# bitbox_rev2_06_sym.net
KiCad netlist of a schematic drawn in EAGLE
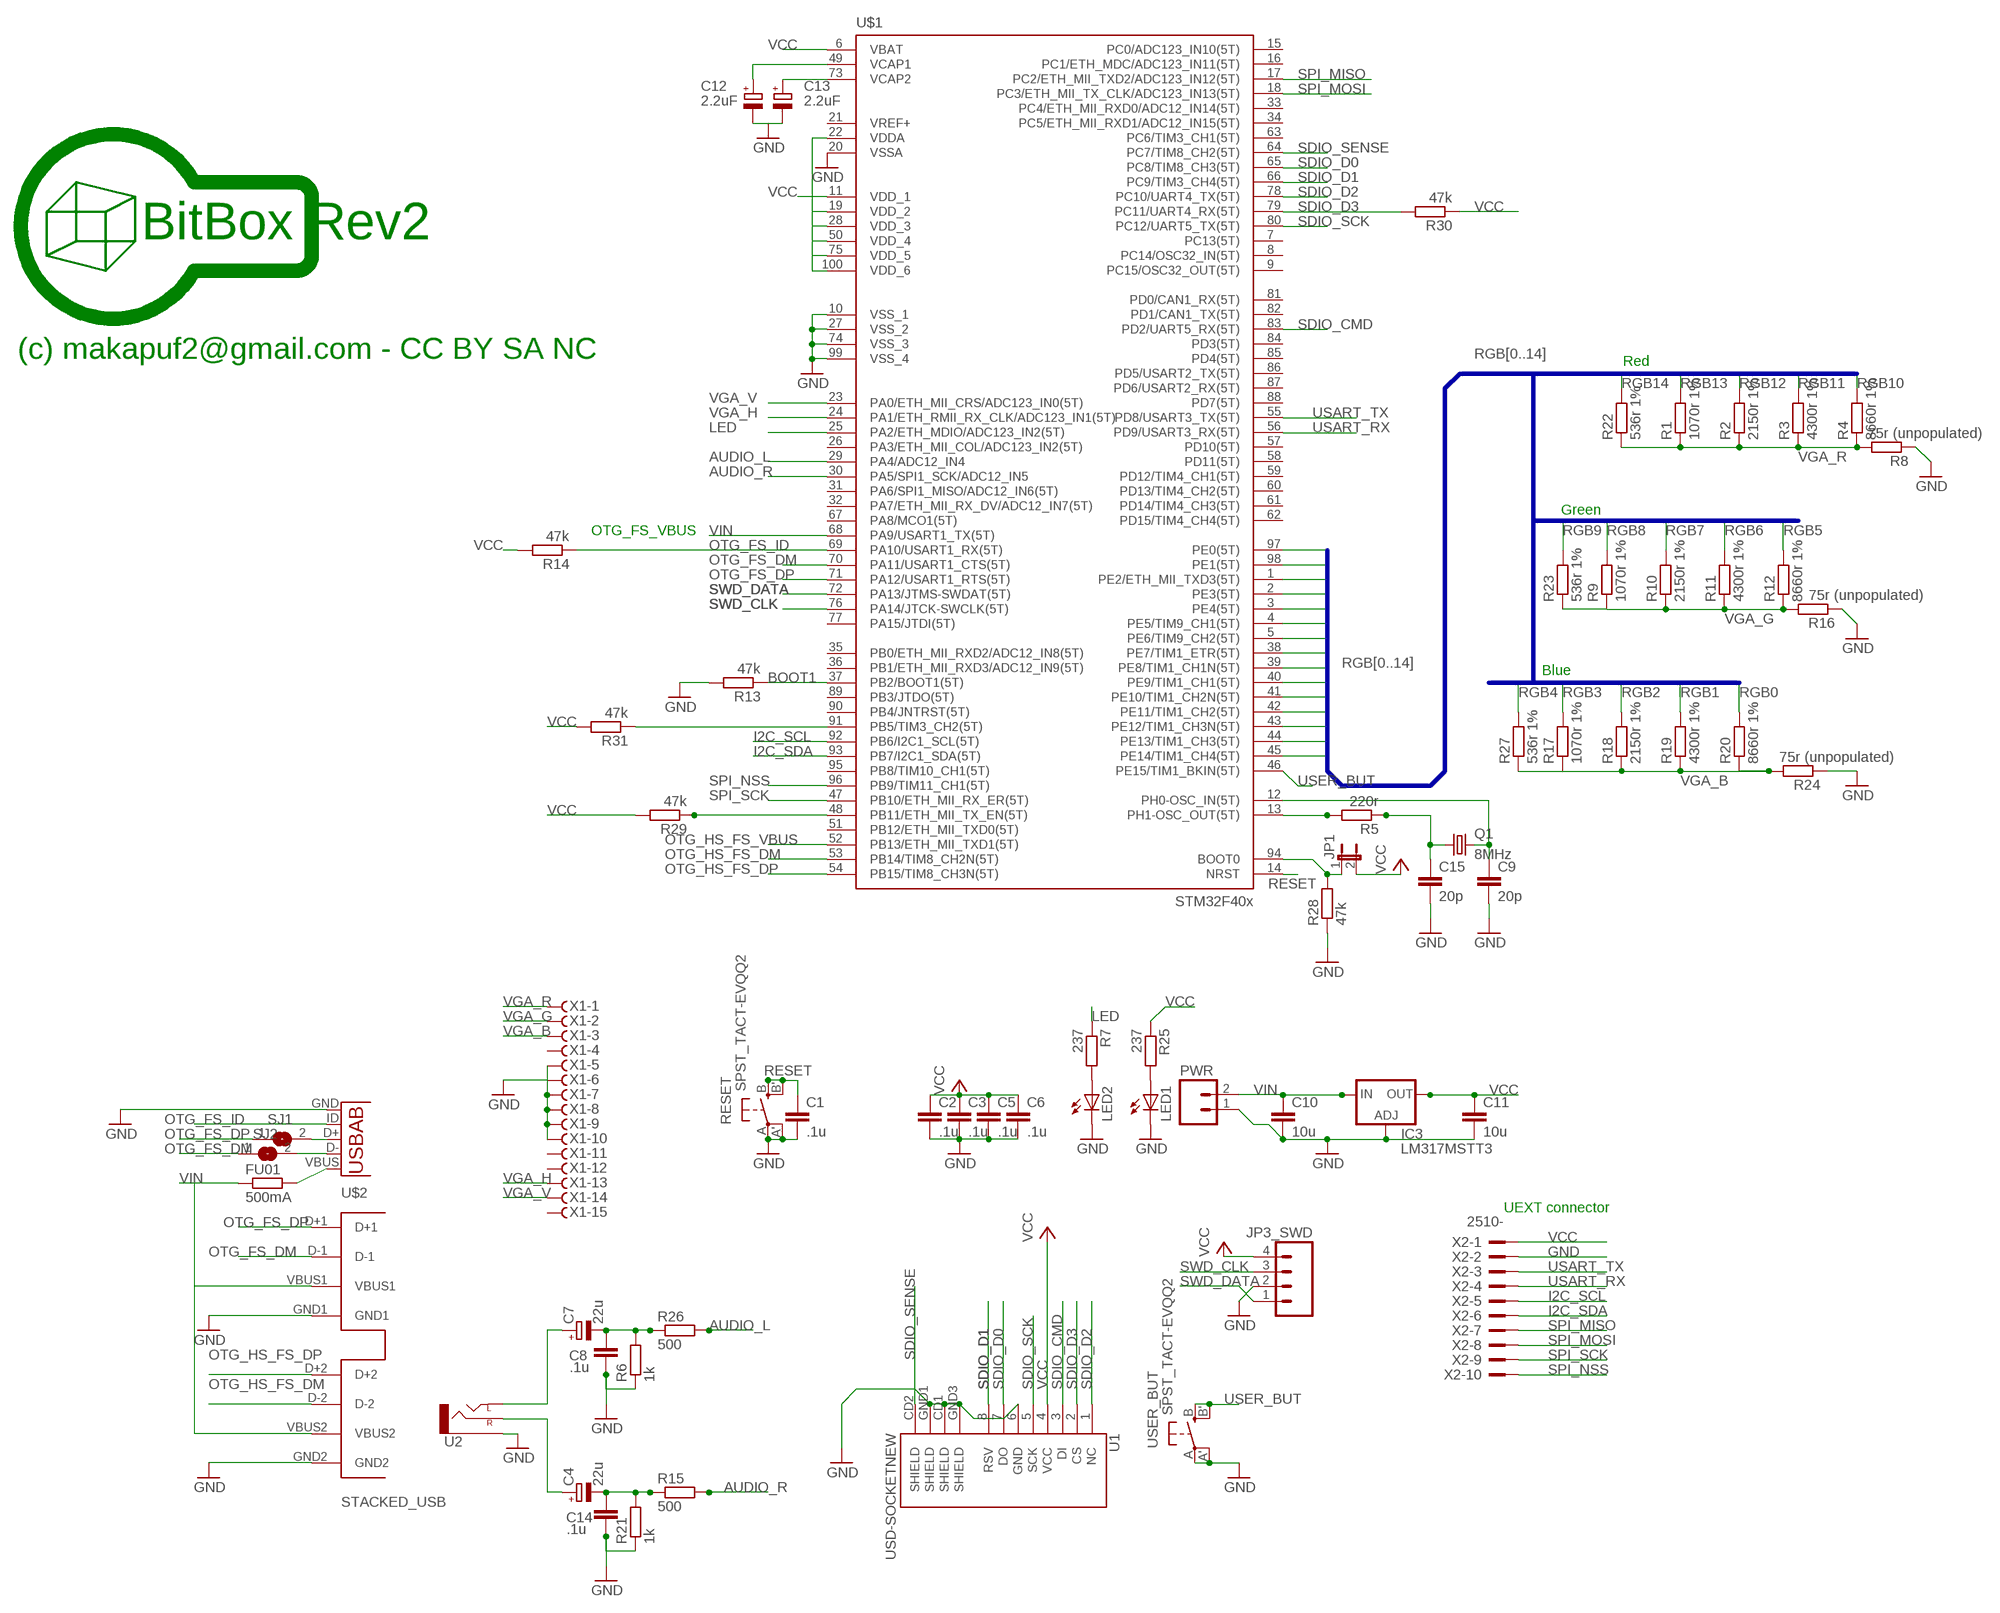
[diagram p0: schematic, sheet 1]

(export (version "E")
  (design (tool "Eeschema 10.0.6"))
  (components
    (comp (ref "C1")
      (value ".1u")
      (footprint "eagle-import:C0603")
      (libsource (lib "eagle-import") (part "C-EUC0603"))
    )
    (comp (ref "C2")
      (value ".1u")
      (footprint "eagle-import:C0603")
      (libsource (lib "eagle-import") (part "C-EUC0603"))
    )
    (comp (ref "C3")
      (value ".1u")
      (footprint "eagle-import:C0603")
      (libsource (lib "eagle-import") (part "C-EUC0603"))
    )
    (comp (ref "C4")
      (value "22u")
      (footprint "eagle-import:153CLV-0505")
      (libsource (lib "eagle-import") (part "CPOL-EU153CLV-0505"))
    )
    (comp (ref "C5")
      (value ".1u")
      (footprint "eagle-import:C0603")
      (libsource (lib "eagle-import") (part "C-EUC0603"))
    )
    (comp (ref "C6")
      (value ".1u")
      (footprint "eagle-import:C0603")
      (libsource (lib "eagle-import") (part "C-EUC0603"))
    )
    (comp (ref "C7")
      (value "22u")
      (footprint "eagle-import:153CLV-0505")
      (libsource (lib "eagle-import") (part "CPOL-EU153CLV-0505"))
    )
    (comp (ref "C8")
      (value ".1u")
      (footprint "eagle-import:C0603")
      (libsource (lib "eagle-import") (part "C-EUC0603"))
    )
    (comp (ref "C9")
      (value "20p")
      (footprint "eagle-import:C0603")
      (libsource (lib "eagle-import") (part "C-EUC0603"))
    )
    (comp (ref "C10")
      (value "10u")
      (footprint "eagle-import:C1206")
      (libsource (lib "eagle-import") (part "C-EUC1206"))
    )
    (comp (ref "C11")
      (value "10u")
      (footprint "eagle-import:C1206")
      (libsource (lib "eagle-import") (part "C-EUC1206"))
    )
    (comp (ref "C12")
      (value "2.2uF")
      (footprint "eagle-import:SMC_B")
      (libsource (lib "eagle-import") (part "CPOL-EUSMCB"))
    )
    (comp (ref "C13")
      (value "2.2uF")
      (footprint "eagle-import:SMC_B")
      (libsource (lib "eagle-import") (part "CPOL-EUSMCB"))
    )
    (comp (ref "C14")
      (value ".1u")
      (footprint "eagle-import:C0603")
      (libsource (lib "eagle-import") (part "C-EUC0603"))
    )
    (comp (ref "C15")
      (value "20p")
      (footprint "eagle-import:C0603")
      (libsource (lib "eagle-import") (part "C-EUC0603"))
    )
    (comp (ref "FU01")
      (value "500mA")
      (footprint "eagle-import:R1206")
      (libsource (lib "eagle-import") (part "R-EU_R1206"))
    )
    (comp (ref "IC3")
      (value "LM317MSTT3")
      (footprint "eagle-import:SOT223")
      (libsource (lib "eagle-import") (part "LM317?MSTT3"))
    )
    (comp (ref "JP1")
      (value "JP1E")
      (footprint "eagle-import:JP1")
      (libsource (lib "eagle-import") (part "JP1E"))
    )
    (comp (ref "JP3_SWD")
      (value "M04PTH")
      (footprint "eagle-import:1X04")
      (libsource (lib "eagle-import") (part "M04PTH"))
    )
    (comp (ref "LED1")
      (value "LEDCHIPLED_0805")
      (footprint "eagle-import:CHIPLED_0805")
      (libsource (lib "eagle-import") (part "LEDCHIPLED_0805"))
    )
    (comp (ref "LED2")
      (value "LEDCHIPLED_0805")
      (footprint "eagle-import:CHIPLED_0805")
      (libsource (lib "eagle-import") (part "LEDCHIPLED_0805"))
    )
    (comp (ref "PWR")
      (value "M02PTH")
      (footprint "eagle-import:1X02")
      (libsource (lib "eagle-import") (part "M02PTH"))
    )
    (comp (ref "Q1")
      (value "8MHz")
      (footprint "eagle-import:SM49")
      (fields (field (name "OC_FARNELL") "unknown"))
      (libsource (lib "eagle-import") (part "CRYSTALSM49"))
    )
    (comp (ref "R1")
      (value "1070r 1%")
      (footprint "eagle-import:R0603")
      (libsource (lib "eagle-import") (part "R-EU_R0603"))
    )
    (comp (ref "R2")
      (value "2150r 1%")
      (footprint "eagle-import:R0603")
      (libsource (lib "eagle-import") (part "R-EU_R0603"))
    )
    (comp (ref "R3")
      (value "4300r 1%")
      (footprint "eagle-import:R0603")
      (libsource (lib "eagle-import") (part "R-EU_R0603"))
    )
    (comp (ref "R4")
      (value "8660r 1%")
      (footprint "eagle-import:R0603")
      (libsource (lib "eagle-import") (part "R-EU_R0603"))
    )
    (comp (ref "R5")
      (value "220r")
      (footprint "eagle-import:R0603")
      (libsource (lib "eagle-import") (part "R-EU_R0603"))
    )
    (comp (ref "R6")
      (value "1k")
      (footprint "eagle-import:R0603")
      (libsource (lib "eagle-import") (part "R-EU_R0603"))
    )
    (comp (ref "R7")
      (value "237")
      (footprint "eagle-import:R0603")
      (libsource (lib "eagle-import") (part "R-EU_R0603"))
    )
    (comp (ref "R8")
      (value "75r (unpopulated)")
      (footprint "eagle-import:R0603")
      (libsource (lib "eagle-import") (part "R-EU_R0603"))
    )
    (comp (ref "R9")
      (value "1070r 1%")
      (footprint "eagle-import:R0603")
      (libsource (lib "eagle-import") (part "R-EU_R0603"))
    )
    (comp (ref "R10")
      (value "2150r 1%")
      (footprint "eagle-import:R0603")
      (libsource (lib "eagle-import") (part "R-EU_R0603"))
    )
    (comp (ref "R11")
      (value "4300r 1%")
      (footprint "eagle-import:R0603")
      (libsource (lib "eagle-import") (part "R-EU_R0603"))
    )
    (comp (ref "R12")
      (value "8660r 1%")
      (footprint "eagle-import:R0603")
      (libsource (lib "eagle-import") (part "R-EU_R0603"))
    )
    (comp (ref "R13")
      (value "47k")
      (footprint "eagle-import:R0603")
      (libsource (lib "eagle-import") (part "R-EU_R0603"))
    )
    (comp (ref "R14")
      (value "47k")
      (footprint "eagle-import:R0603")
      (libsource (lib "eagle-import") (part "R-EU_R0603"))
    )
    (comp (ref "R15")
      (value "500")
      (footprint "eagle-import:R0603")
      (libsource (lib "eagle-import") (part "R-EU_R0603"))
    )
    (comp (ref "R16")
      (value "75r (unpopulated)")
      (footprint "eagle-import:R0603")
      (libsource (lib "eagle-import") (part "R-EU_R0603"))
    )
    (comp (ref "R17")
      (value "1070r 1%")
      (footprint "eagle-import:R0603")
      (libsource (lib "eagle-import") (part "R-EU_R0603"))
    )
    (comp (ref "R18")
      (value "2150r 1%")
      (footprint "eagle-import:R0603")
      (libsource (lib "eagle-import") (part "R-EU_R0603"))
    )
    (comp (ref "R19")
      (value "4300r 1%")
      (footprint "eagle-import:R0603")
      (libsource (lib "eagle-import") (part "R-EU_R0603"))
    )
    (comp (ref "R20")
      (value "8660r 1%")
      (footprint "eagle-import:R0603")
      (libsource (lib "eagle-import") (part "R-EU_R0603"))
    )
    (comp (ref "R21")
      (value "1k")
      (footprint "eagle-import:R0603")
      (libsource (lib "eagle-import") (part "R-EU_R0603"))
    )
    (comp (ref "R22")
      (value "536r 1%")
      (footprint "eagle-import:R0603")
      (libsource (lib "eagle-import") (part "R-EU_R0603"))
    )
    (comp (ref "R23")
      (value "536r 1%")
      (footprint "eagle-import:R0603")
      (libsource (lib "eagle-import") (part "R-EU_R0603"))
    )
    (comp (ref "R24")
      (value "75r (unpopulated)")
      (footprint "eagle-import:R0603")
      (libsource (lib "eagle-import") (part "R-EU_R0603"))
    )
    (comp (ref "R25")
      (value "237")
      (footprint "eagle-import:R0603")
      (libsource (lib "eagle-import") (part "R-EU_R0603"))
    )
    (comp (ref "R26")
      (value "500")
      (footprint "eagle-import:R0603")
      (libsource (lib "eagle-import") (part "R-EU_R0603"))
    )
    (comp (ref "R27")
      (value "536r 1%")
      (footprint "eagle-import:R0603")
      (libsource (lib "eagle-import") (part "R-EU_R0603"))
    )
    (comp (ref "R28")
      (value "47k")
      (footprint "eagle-import:R0603")
      (libsource (lib "eagle-import") (part "R-EU_R0603"))
    )
    (comp (ref "R29")
      (value "47k")
      (footprint "eagle-import:R0603")
      (libsource (lib "eagle-import") (part "R-EU_R0603"))
    )
    (comp (ref "R30")
      (value "47k")
      (footprint "eagle-import:R0603")
      (libsource (lib "eagle-import") (part "R-EU_R0603"))
    )
    (comp (ref "R31")
      (value "47k")
      (footprint "eagle-import:R0603")
      (libsource (lib "eagle-import") (part "R-EU_R0603"))
    )
    (comp (ref "RESET")
      (value "SPST_TACT-EVQQ2")
      (footprint "eagle-import:EVQ-Q2")
      (libsource (lib "eagle-import") (part "SPST_TACT-EVQQ2"))
    )
    (comp (ref "SJ1") (value "SJ") (footprint "eagle-import:SJ") (libsource (lib "eagle-import") (part "SJ")))
    (comp (ref "SJ2") (value "SJ") (footprint "eagle-import:SJ") (libsource (lib "eagle-import") (part "SJ")))
    (comp (ref "U$1")
      (value "STM32F407V")
      (footprint "eagle-import:TQFP100")
      (libsource (lib "eagle-import") (part "STM32F407V"))
    )
    (comp (ref "U$2")
      (value "STACKED_USB")
      (footprint "eagle-import:2STACKED")
      (libsource (lib "eagle-import") (part "STACKED_USB"))
    )
    (comp (ref "U1")
      (value "USD-SOCKETNEW")
      (footprint "eagle-import:MICRO-SD-SOCKET-PP")
      (libsource (lib "eagle-import") (part "USD-SOCKETNEW"))
    )
    (comp (ref "U2")
      (value "AUDIO-JACKPTH")
      (footprint "eagle-import:AUDIO-JACK")
      (libsource (lib "eagle-import") (part "AUDIO-JACKPTH"))
    )
    (comp (ref "U3")
      (value "USB-AB")
      (footprint "eagle-import:USB-AB-MICRO-SMD")
      (libsource (lib "eagle-import") (part "USB-AB"))
    )
    (comp (ref "USER_BUT")
      (value "SPST_TACT-EVQQ2")
      (footprint "eagle-import:EVQ-Q2")
      (libsource (lib "eagle-import") (part "SPST_TACT-EVQQ2"))
    )
    (comp (ref "X1")
      (value "HF15HS")
      (footprint "eagle-import:HDF15H")
      (libsource (lib "eagle-import") (part "HF15?SH"))
    )
    (comp (ref "X2")
      (value "2510-")
      (footprint "eagle-import:PAK100_2500-10")
      (fields (field (name "MF") "3M") (field (name "MPN") "2510-6002UB"))
      (libsource (lib "eagle-import") (part "2510-"))
    )
  )
  (nets
    (net (code "1") (name "/AUDIO_L") (class "Default")
      (node (ref "R26") (pin "2") (pinfunction "2_2") (pintype "passive"))
      (node (ref "U$1") (pin "29") (pinfunction "PA4/ADC12_IN4_29") (pintype "bidirectional"))
    )
    (net (code "2") (name "/AUDIO_R") (class "Default")
      (node (ref "R15") (pin "2") (pinfunction "2_2") (pintype "passive"))
      (node (ref "U$1") (pin "30") (pinfunction "PA5/SPI1_SCK/ADC12_IN5_30") (pintype "bidirectional"))
    )
    (net (code "3") (name "/BOOT1") (class "Default")
      (node (ref "R13") (pin "1") (pinfunction "1_1") (pintype "passive"))
      (node (ref "U$1") (pin "37") (pinfunction "PB2/BOOT1(5T)_37") (pintype "bidirectional"))
    )
    (net (code "4") (name "/I2C_SCL") (class "Default")
      (node (ref "U$1") (pin "92") (pinfunction "PB6/I2C1_SCL(5T)_92") (pintype "bidirectional"))
      (node (ref "X2") (pin "5") (pinfunction "KL_5") (pintype "passive"))
    )
    (net (code "5") (name "/I2C_SDA") (class "Default")
      (node (ref "U$1") (pin "93") (pinfunction "PB7/I2C1_SDA(5T)_93") (pintype "bidirectional"))
      (node (ref "X2") (pin "6") (pinfunction "KL_6") (pintype "passive"))
    )
    (net (code "6") (name "/LED") (class "Default")
      (node (ref "R7") (pin "1") (pinfunction "1_1") (pintype "passive"))
      (node (ref "U$1") (pin "25") (pinfunction "PA2/ETH_MDIO/ADC123_IN2(5T)_25") (pintype "bidirectional"))
    )
    (net (code "7") (name "/OTG_FS_DM") (class "Default")
      (node (ref "SJ2") (pin "1") (pinfunction "1_1") (pintype "passive"))
      (node (ref "U$1") (pin "70") (pinfunction "PA11/USART1_CTS(5T)_70") (pintype "bidirectional"))
      (node (ref "U$2") (pin "D-1") (pinfunction "D-1_D-1") (pintype "bidirectional"))
    )
    (net (code "8") (name "/OTG_FS_DP") (class "Default")
      (node (ref "SJ1") (pin "1") (pinfunction "1_1") (pintype "passive"))
      (node (ref "U$1") (pin "71") (pinfunction "PA12/USART1_RTS(5T)_71") (pintype "bidirectional"))
      (node (ref "U$2") (pin "D+1") (pinfunction "D+1_D+1") (pintype "bidirectional"))
    )
    (net (code "9") (name "/OTG_FS_ID") (class "Default")
      (node (ref "R14") (pin "1") (pinfunction "1_1") (pintype "passive"))
      (node (ref "U$1") (pin "69") (pinfunction "PA10/USART1_RX(5T)_69") (pintype "bidirectional"))
      (node (ref "U3") (pin "ID") (pinfunction "USBID_ID") (pintype "bidirectional"))
    )
    (net (code "10") (name "/OTG_HS_FS_DM") (class "Default")
      (node (ref "U$1") (pin "53") (pinfunction "PB14/TIM8_CH2N(5T)_53") (pintype "bidirectional"))
      (node (ref "U$2") (pin "D-2") (pinfunction "D-2_D-2") (pintype "bidirectional"))
    )
    (net (code "11") (name "/OTG_HS_FS_DP") (class "Default")
      (node (ref "U$1") (pin "54") (pinfunction "PB15/TIM8_CH3N(5T)_54") (pintype "bidirectional"))
      (node (ref "U$2") (pin "D+2") (pinfunction "D+2_D+2") (pintype "bidirectional"))
    )
    (net (code "12") (name "/OTG_HS_FS_VBUS") (class "Default")
      (node (ref "U$1") (pin "52") (pinfunction "PB13/ETH_MII_TXD1(5T)_52") (pintype "bidirectional"))
    )
    (net (code "13") (name "/RESET") (class "Default")
      (node (ref "C1") (pin "1") (pinfunction "1_1") (pintype "passive"))
      (node (ref "RESET") (pin "B") (pinfunction "S_B") (pintype "passive"))
      (node (ref "RESET") (pin "B'") (pinfunction "S1_B'") (pintype "passive"))
      (node (ref "U$1") (pin "14") (pinfunction "NRST_14") (pintype "bidirectional"))
    )
    (net (code "14") (name "/RGB0") (class "Default")
      (node (ref "R20") (pin "2") (pinfunction "2_2") (pintype "passive"))
      (node (ref "U$1") (pin "97") (pinfunction "PE0(5T)_97") (pintype "bidirectional"))
    )
    (net (code "15") (name "/RGB1") (class "Default")
      (node (ref "R19") (pin "2") (pinfunction "2_2") (pintype "passive"))
      (node (ref "U$1") (pin "98") (pinfunction "PE1(5T)_98") (pintype "bidirectional"))
    )
    (net (code "16") (name "/RGB2") (class "Default")
      (node (ref "R18") (pin "2") (pinfunction "2_2") (pintype "passive"))
      (node (ref "U$1") (pin "1") (pinfunction "PE2/ETH_MII_TXD3(5T)_1") (pintype "bidirectional"))
    )
    (net (code "17") (name "/RGB3") (class "Default")
      (node (ref "R17") (pin "2") (pinfunction "2_2") (pintype "passive"))
      (node (ref "U$1") (pin "2") (pinfunction "PE3(5T)_2") (pintype "bidirectional"))
    )
    (net (code "18") (name "/RGB4") (class "Default")
      (node (ref "R27") (pin "2") (pinfunction "2_2") (pintype "passive"))
      (node (ref "U$1") (pin "3") (pinfunction "PE4(5T)_3") (pintype "bidirectional"))
    )
    (net (code "19") (name "/RGB5") (class "Default")
      (node (ref "R12") (pin "2") (pinfunction "2_2") (pintype "passive"))
      (node (ref "U$1") (pin "4") (pinfunction "PE5/TIM9_CH1(5T)_4") (pintype "bidirectional"))
    )
    (net (code "20") (name "/RGB6") (class "Default")
      (node (ref "R11") (pin "2") (pinfunction "2_2") (pintype "passive"))
      (node (ref "U$1") (pin "5") (pinfunction "PE6/TIM9_CH2(5T)_5") (pintype "bidirectional"))
    )
    (net (code "21") (name "/RGB7") (class "Default")
      (node (ref "R10") (pin "2") (pinfunction "2_2") (pintype "passive"))
      (node (ref "U$1") (pin "38") (pinfunction "PE7/TIM1_ETR(5T)_38") (pintype "bidirectional"))
    )
    (net (code "22") (name "/RGB8") (class "Default")
      (node (ref "R9") (pin "2") (pinfunction "2_2") (pintype "passive"))
      (node (ref "U$1") (pin "39") (pinfunction "PE8/TIM1_CH1N(5T)_39") (pintype "bidirectional"))
    )
    (net (code "23") (name "/RGB9") (class "Default")
      (node (ref "R23") (pin "2") (pinfunction "2_2") (pintype "passive"))
      (node (ref "U$1") (pin "40") (pinfunction "PE9/TIM1_CH1(5T)_40") (pintype "bidirectional"))
    )
    (net (code "24") (name "/RGB10") (class "Default")
      (node (ref "R4") (pin "2") (pinfunction "2_2") (pintype "passive"))
      (node (ref "U$1") (pin "41") (pinfunction "PE10/TIM1_CH2N(5T)_41") (pintype "bidirectional"))
    )
    (net (code "25") (name "/RGB11") (class "Default")
      (node (ref "R3") (pin "2") (pinfunction "2_2") (pintype "passive"))
      (node (ref "U$1") (pin "42") (pinfunction "PE11/TIM1_CH2(5T)_42") (pintype "bidirectional"))
    )
    (net (code "26") (name "/RGB12") (class "Default")
      (node (ref "R2") (pin "2") (pinfunction "2_2") (pintype "passive"))
      (node (ref "U$1") (pin "43") (pinfunction "PE12/TIM1_CH3N(5T)_43") (pintype "bidirectional"))
    )
    (net (code "27") (name "/RGB13") (class "Default")
      (node (ref "R1") (pin "2") (pinfunction "2_2") (pintype "passive"))
      (node (ref "U$1") (pin "44") (pinfunction "PE13/TIM1_CH3(5T)_44") (pintype "bidirectional"))
    )
    (net (code "28") (name "/RGB14") (class "Default")
      (node (ref "R22") (pin "2") (pinfunction "2_2") (pintype "passive"))
      (node (ref "U$1") (pin "45") (pinfunction "PE14/TIM1_CH4(5T)_45") (pintype "bidirectional"))
    )
    (net (code "30") (name "/SDIO_CMD") (class "Default")
      (node (ref "U$1") (pin "83") (pinfunction "PD2/UART5_RX(5T)_83") (pintype "bidirectional"))
      (node (ref "U1") (pin "3") (pinfunction "DI_3") (pintype "bidirectional"))
    )
    (net (code "31") (name "/SDIO_D0") (class "Default")
      (node (ref "U$1") (pin "65") (pinfunction "PC8/TIM8_CH3(5T)_65") (pintype "bidirectional"))
      (node (ref "U1") (pin "7") (pinfunction "DO_7") (pintype "bidirectional"))
    )
    (net (code "32") (name "/SDIO_D1") (class "Default")
      (node (ref "U$1") (pin "66") (pinfunction "PC9/TIM3_CH4(5T)_66") (pintype "bidirectional"))
      (node (ref "U1") (pin "8") (pinfunction "RSV_8") (pintype "bidirectional"))
    )
    (net (code "33") (name "/SDIO_D2") (class "Default")
      (node (ref "U$1") (pin "78") (pinfunction "PC10/UART4_TX(5T)_78") (pintype "bidirectional"))
      (node (ref "U1") (pin "1") (pinfunction "NC_1") (pintype "bidirectional"))
    )
    (net (code "34") (name "/SDIO_D3") (class "Default")
      (node (ref "R30") (pin "2") (pinfunction "2_2") (pintype "passive"))
      (node (ref "U$1") (pin "79") (pinfunction "PC11/UART4_RX(5T)_79") (pintype "bidirectional"))
      (node (ref "U1") (pin "2") (pinfunction "CS_2") (pintype "bidirectional"))
    )
    (net (code "35") (name "/SDIO_SCK") (class "Default")
      (node (ref "U$1") (pin "80") (pinfunction "PC12/UART5_TX(5T)_80") (pintype "bidirectional"))
      (node (ref "U1") (pin "5") (pinfunction "SCK_5") (pintype "bidirectional"))
    )
    (net (code "36") (name "/SDIO_SENSE") (class "Default")
      (node (ref "U$1") (pin "64") (pinfunction "PC7/TIM8_CH2(5T)_64") (pintype "bidirectional"))
      (node (ref "U1") (pin "CD2") (pinfunction "SHIELD_CD2") (pintype "bidirectional"))
    )
    (net (code "37") (name "/SPI_MISO") (class "Default")
      (node (ref "U$1") (pin "17") (pinfunction "PC2/ETH_MII_TXD2/ADC123_IN12(5T)_17") (pintype "bidirectional"))
      (node (ref "X2") (pin "7") (pinfunction "KL_7") (pintype "passive"))
    )
    (net (code "38") (name "/SPI_MOSI") (class "Default")
      (node (ref "U$1") (pin "18") (pinfunction "PC3/ETH_MII_TX_CLK/ADC123_IN13(5T)_18") (pintype "bidirectional"))
      (node (ref "X2") (pin "8") (pinfunction "KL_8") (pintype "passive"))
    )
    (net (code "39") (name "/SPI_NSS") (class "Default")
      (node (ref "U$1") (pin "96") (pinfunction "PB9/TIM11_CH1(5T)_96") (pintype "bidirectional"))
      (node (ref "X2") (pin "10") (pinfunction "KL_10") (pintype "passive"))
    )
    (net (code "40") (name "/SPI_SCK") (class "Default")
      (node (ref "U$1") (pin "47") (pinfunction "PB10/ETH_MII_RX_ER(5T)_47") (pintype "bidirectional"))
      (node (ref "X2") (pin "9") (pinfunction "KL_9") (pintype "passive"))
    )
    (net (code "41") (name "/SWD_CLK") (class "Default")
      (node (ref "JP3_SWD") (pin "3") (pinfunction "3_3") (pintype "passive"))
      (node (ref "U$1") (pin "76") (pinfunction "PA14/JTCK-SWCLK(5T)_76") (pintype "bidirectional"))
    )
    (net (code "42") (name "/SWD_DATA") (class "Default")
      (node (ref "JP3_SWD") (pin "1") (pinfunction "1_1") (pintype "passive"))
      (node (ref "U$1") (pin "72") (pinfunction "PA13/JTMS-SWDAT(5T)_72") (pintype "bidirectional"))
    )
    (net (code "43") (name "/USART_RX") (class "Default")
      (node (ref "U$1") (pin "56") (pinfunction "PD9/USART3_RX(5T)_56") (pintype "bidirectional"))
      (node (ref "X2") (pin "4") (pinfunction "KL_4") (pintype "passive"))
    )
    (net (code "44") (name "/USART_TX") (class "Default")
      (node (ref "U$1") (pin "55") (pinfunction "PD8/USART3_TX(5T)_55") (pintype "bidirectional"))
      (node (ref "X2") (pin "3") (pinfunction "KL_3") (pintype "passive"))
    )
    (net (code "45") (name "/USER_BUT") (class "Default")
      (node (ref "U$1") (pin "46") (pinfunction "PE15/TIM1_BKIN(5T)_46") (pintype "bidirectional"))
      (node (ref "USER_BUT") (pin "B") (pinfunction "S_B") (pintype "passive"))
      (node (ref "USER_BUT") (pin "B'") (pinfunction "S1_B'") (pintype "passive"))
    )
    (net (code "46") (name "/VGA_B") (class "Default")
      (node (ref "R17") (pin "1") (pinfunction "1_1") (pintype "passive"))
      (node (ref "R18") (pin "1") (pinfunction "1_1") (pintype "passive"))
      (node (ref "R19") (pin "1") (pinfunction "1_1") (pintype "passive"))
      (node (ref "R20") (pin "1") (pinfunction "1_1") (pintype "passive"))
      (node (ref "R24") (pin "2") (pinfunction "2_2") (pintype "passive"))
      (node (ref "R27") (pin "1") (pinfunction "1_1") (pintype "passive"))
      (node (ref "X1") (pin "3") (pinfunction "F_3") (pintype "passive"))
    )
    (net (code "47") (name "/VGA_G") (class "Default")
      (node (ref "R10") (pin "1") (pinfunction "1_1") (pintype "passive"))
      (node (ref "R11") (pin "1") (pinfunction "1_1") (pintype "passive"))
      (node (ref "R12") (pin "1") (pinfunction "1_1") (pintype "passive"))
      (node (ref "R16") (pin "2") (pinfunction "2_2") (pintype "passive"))
      (node (ref "R23") (pin "1") (pinfunction "1_1") (pintype "passive"))
      (node (ref "R9") (pin "1") (pinfunction "1_1") (pintype "passive"))
      (node (ref "X1") (pin "2") (pinfunction "F_2") (pintype "passive"))
    )
    (net (code "48") (name "/VGA_H") (class "Default")
      (node (ref "U$1") (pin "24") (pinfunction "PA1/ETH_RMII_RX_CLK/ADC123_IN1(5T)_24") (pintype "bidirectional"))
      (node (ref "X1") (pin "13") (pinfunction "F_13") (pintype "passive"))
    )
    (net (code "49") (name "/VGA_R") (class "Default")
      (node (ref "R1") (pin "1") (pinfunction "1_1") (pintype "passive"))
      (node (ref "R2") (pin "1") (pinfunction "1_1") (pintype "passive"))
      (node (ref "R22") (pin "1") (pinfunction "1_1") (pintype "passive"))
      (node (ref "R3") (pin "1") (pinfunction "1_1") (pintype "passive"))
      (node (ref "R4") (pin "1") (pinfunction "1_1") (pintype "passive"))
      (node (ref "R8") (pin "2") (pinfunction "2_2") (pintype "passive"))
      (node (ref "X1") (pin "1") (pinfunction "F_1") (pintype "passive"))
    )
    (net (code "50") (name "/VGA_V") (class "Default")
      (node (ref "U$1") (pin "23") (pinfunction "PA0/ETH_MII_CRS/ADC123_IN0(5T)_23") (pintype "bidirectional"))
      (node (ref "X1") (pin "14") (pinfunction "F_14") (pintype "passive"))
    )
    (net (code "51") (name "/VIN") (class "Default")
      (node (ref "C10") (pin "1") (pinfunction "1_1") (pintype "passive"))
      (node (ref "FU01") (pin "1") (pinfunction "1_1") (pintype "passive"))
      (node (ref "IC3") (pin "3") (pinfunction "IN_3") (pintype "input"))
      (node (ref "PWR") (pin "2") (pinfunction "2_2") (pintype "passive"))
      (node (ref "U$1") (pin "68") (pinfunction "PA9/USART1_TX(5T)_68") (pintype "bidirectional"))
      (node (ref "U$2") (pin "VBUS1") (pinfunction "VBUS1_VBUS1") (pintype "bidirectional"))
      (node (ref "U$2") (pin "VBUS2") (pinfunction "VBUS2_VBUS2") (pintype "bidirectional"))
    )
    (net (code "52") (name "GND") (class "Default")
      (node (ref "C1") (pin "2") (pinfunction "2_2") (pintype "passive"))
      (node (ref "C10") (pin "2") (pinfunction "2_2") (pintype "passive"))
      (node (ref "C11") (pin "2") (pinfunction "2_2") (pintype "passive"))
      (node (ref "C12") (pin "-") (pinfunction "-_-") (pintype "passive"))
      (node (ref "C13") (pin "-") (pinfunction "-_-") (pintype "passive"))
      (node (ref "C14") (pin "2") (pinfunction "2_2") (pintype "passive"))
      (node (ref "C15") (pin "2") (pinfunction "2_2") (pintype "passive"))
      (node (ref "C2") (pin "2") (pinfunction "2_2") (pintype "passive"))
      (node (ref "C3") (pin "2") (pinfunction "2_2") (pintype "passive"))
      (node (ref "C5") (pin "2") (pinfunction "2_2") (pintype "passive"))
      (node (ref "C6") (pin "2") (pinfunction "2_2") (pintype "passive"))
      (node (ref "C8") (pin "2") (pinfunction "2_2") (pintype "passive"))
      (node (ref "C9") (pin "2") (pinfunction "2_2") (pintype "passive"))
      (node (ref "IC3") (pin "1") (pinfunction "ADJ_1") (pintype "input"))
      (node (ref "JP3_SWD") (pin "2") (pinfunction "2_2") (pintype "passive"))
      (node (ref "LED1") (pin "C") (pinfunction "C_C") (pintype "passive"))
      (node (ref "LED2") (pin "C") (pinfunction "C_C") (pintype "passive"))
      (node (ref "PWR") (pin "1") (pinfunction "1_1") (pintype "passive"))
      (node (ref "R13") (pin "2") (pinfunction "2_2") (pintype "passive"))
      (node (ref "R16") (pin "1") (pinfunction "1_1") (pintype "passive"))
      (node (ref "R21") (pin "1") (pinfunction "1_1") (pintype "passive"))
      (node (ref "R24") (pin "1") (pinfunction "1_1") (pintype "passive"))
      (node (ref "R28") (pin "1") (pinfunction "1_1") (pintype "passive"))
      (node (ref "R6") (pin "1") (pinfunction "1_1") (pintype "passive"))
      (node (ref "R8") (pin "1") (pinfunction "1_1") (pintype "passive"))
      (node (ref "RESET") (pin "A") (pinfunction "P_A") (pintype "passive"))
      (node (ref "RESET") (pin "A'") (pinfunction "P1_A'") (pintype "passive"))
      (node (ref "U$1") (pin "10") (pinfunction "VSS_1_10") (pintype "bidirectional"))
      (node (ref "U$1") (pin "20") (pinfunction "VSSA_20") (pintype "bidirectional"))
      (node (ref "U$1") (pin "27") (pinfunction "VSS_2_27") (pintype "bidirectional"))
      (node (ref "U$1") (pin "74") (pinfunction "VSS_3_74") (pintype "bidirectional"))
      (node (ref "U$1") (pin "99") (pinfunction "VSS_4_99") (pintype "bidirectional"))
      (node (ref "U$2") (pin "GND1") (pinfunction "GND1_GND1") (pintype "bidirectional"))
      (node (ref "U$2") (pin "GND2") (pinfunction "GND2_GND2") (pintype "bidirectional"))
      (node (ref "U1") (pin "6") (pinfunction "GND_6") (pintype "bidirectional"))
      (node (ref "U1") (pin "CD1") (pinfunction "SHIELD_CD1") (pintype "bidirectional"))
      (node (ref "U1") (pin "GND1") (pinfunction "SHIELD_GND1") (pintype "bidirectional"))
      (node (ref "U1") (pin "GND3") (pinfunction "SHIELD_GND3") (pintype "bidirectional"))
      (node (ref "U2") (pin "SLEEVE") (pinfunction "SLEEVE_SLEEVE") (pintype "bidirectional"))
      (node (ref "U3") (pin "GND") (pinfunction "GND_GND") (pintype "bidirectional"))
      (node (ref "USER_BUT") (pin "A") (pinfunction "P_A") (pintype "passive"))
      (node (ref "USER_BUT") (pin "A'") (pinfunction "P1_A'") (pintype "passive"))
      (node (ref "X1") (pin "10") (pinfunction "F_10") (pintype "passive"))
      (node (ref "X1") (pin "5") (pinfunction "F_5") (pintype "passive"))
      (node (ref "X1") (pin "6") (pinfunction "F_6") (pintype "passive"))
      (node (ref "X1") (pin "7") (pinfunction "F_7") (pintype "passive"))
      (node (ref "X1") (pin "8") (pinfunction "F_8") (pintype "passive"))
      (node (ref "X1") (pin "9") (pinfunction "F_9") (pintype "passive"))
      (node (ref "X2") (pin "2") (pinfunction "KL_2") (pintype "passive"))
    )
    (net (code "53") (name "Net-(C7-Pad-)") (class "Default")
      (node (ref "C7") (pin "-") (pinfunction "-_-") (pintype "passive"))
      (node (ref "C8") (pin "1") (pinfunction "1_1") (pintype "passive"))
      (node (ref "R26") (pin "1") (pinfunction "1_1") (pintype "passive"))
      (node (ref "R6") (pin "2") (pinfunction "2_2") (pintype "passive"))
    )
    (net (code "54") (name "Net-(C14-Pad1)") (class "Default")
      (node (ref "C14") (pin "1") (pinfunction "1_1") (pintype "passive"))
      (node (ref "C4") (pin "-") (pinfunction "-_-") (pintype "passive"))
      (node (ref "R15") (pin "1") (pinfunction "1_1") (pintype "passive"))
      (node (ref "R21") (pin "2") (pinfunction "2_2") (pintype "passive"))
    )
    (net (code "55") (name "Net-(C15-Pad1)") (class "Default")
      (node (ref "C15") (pin "1") (pinfunction "1_1") (pintype "passive"))
      (node (ref "Q1") (pin "1") (pinfunction "1_1") (pintype "passive"))
      (node (ref "R5") (pin "1") (pinfunction "1_1") (pintype "passive"))
    )
    (net (code "56") (name "Net-(FU01-Pad2)") (class "Default")
      (node (ref "FU01") (pin "2") (pinfunction "2_2") (pintype "passive"))
      (node (ref "U3") (pin "VBUS") (pinfunction "VBUS_VBUS") (pintype "bidirectional"))
    )
    (net (code "57") (name "Net-(LED1-PadA)") (class "Default")
      (node (ref "LED1") (pin "A") (pinfunction "A_A") (pintype "passive"))
      (node (ref "R25") (pin "2") (pinfunction "2_2") (pintype "passive"))
    )
    (net (code "58") (name "Net-(LED2-PadA)") (class "Default")
      (node (ref "LED2") (pin "A") (pinfunction "A_A") (pintype "passive"))
      (node (ref "R7") (pin "2") (pinfunction "2_2") (pintype "passive"))
    )
    (net (code "59") (name "Net-(SJ1-Pad2)") (class "Default")
      (node (ref "SJ1") (pin "2") (pinfunction "2_2") (pintype "passive"))
      (node (ref "U3") (pin "D+") (pinfunction "D+_D+") (pintype "bidirectional"))
    )
    (net (code "60") (name "Net-(SJ2-Pad2)") (class "Default")
      (node (ref "SJ2") (pin "2") (pinfunction "2_2") (pintype "passive"))
      (node (ref "U3") (pin "D-") (pinfunction "D-_D-") (pintype "bidirectional"))
    )
    (net (code "61") (name "Net-(U$1-BOOT0)") (class "Default")
      (node (ref "JP1") (pin "1") (pinfunction "1_1") (pintype "passive"))
      (node (ref "R28") (pin "2") (pinfunction "2_2") (pintype "passive"))
      (node (ref "U$1") (pin "94") (pinfunction "BOOT0_94") (pintype "bidirectional"))
    )
    (net (code "62") (name "Net-(U$1-PB5{slash}TIM3_CH2(5T))") (class "Default")
      (node (ref "R31") (pin "1") (pinfunction "1_1") (pintype "passive"))
      (node (ref "U$1") (pin "91") (pinfunction "PB5/TIM3_CH2(5T)_91") (pintype "bidirectional"))
    )
    (net (code "63") (name "Net-(U$1-PB11{slash}ETH_MII_TX_EN(5T))") (class "Default")
      (node (ref "R29") (pin "1") (pinfunction "1_1") (pintype "passive"))
      (node (ref "U$1") (pin "48") (pinfunction "PB11/ETH_MII_TX_EN(5T)_48") (pintype "bidirectional"))
    )
    (net (code "64") (name "Net-(U$1-PH0-OSC_IN(5T))") (class "Default")
      (node (ref "C9") (pin "1") (pinfunction "1_1") (pintype "passive"))
      (node (ref "Q1") (pin "2") (pinfunction "2_2") (pintype "passive"))
      (node (ref "U$1") (pin "12") (pinfunction "PH0-OSC_IN(5T)_12") (pintype "bidirectional"))
    )
    (net (code "65") (name "Net-(U$1-PH1-OSC_OUT(5T))") (class "Default")
      (node (ref "R5") (pin "2") (pinfunction "2_2") (pintype "passive"))
      (node (ref "U$1") (pin "13") (pinfunction "PH1-OSC_OUT(5T)_13") (pintype "bidirectional"))
    )
    (net (code "66") (name "Net-(U$1-VCAP1)") (class "Default")
      (node (ref "C12") (pin "+") (pinfunction "+_+") (pintype "passive"))
      (node (ref "U$1") (pin "49") (pinfunction "VCAP1_49") (pintype "bidirectional"))
    )
    (net (code "67") (name "Net-(U$1-VCAP2)") (class "Default")
      (node (ref "C13") (pin "+") (pinfunction "+_+") (pintype "passive"))
      (node (ref "U$1") (pin "73") (pinfunction "VCAP2_73") (pintype "bidirectional"))
    )
    (net (code "68") (name "Net-(U2-LEFT)") (class "Default")
      (node (ref "C7") (pin "+") (pinfunction "+_+") (pintype "passive"))
      (node (ref "U2") (pin "TIP") (pinfunction "LEFT_TIP") (pintype "bidirectional"))
    )
    (net (code "69") (name "Net-(U2-RIGHT)") (class "Default")
      (node (ref "C4") (pin "+") (pinfunction "+_+") (pintype "passive"))
      (node (ref "U2") (pin "RING") (pinfunction "RIGHT_RING") (pintype "bidirectional"))
    )
    (net (code "70") (name "VCC") (class "Default")
      (node (ref "C11") (pin "1") (pinfunction "1_1") (pintype "passive"))
      (node (ref "C2") (pin "1") (pinfunction "1_1") (pintype "passive"))
      (node (ref "C3") (pin "1") (pinfunction "1_1") (pintype "passive"))
      (node (ref "C5") (pin "1") (pinfunction "1_1") (pintype "passive"))
      (node (ref "C6") (pin "1") (pinfunction "1_1") (pintype "passive"))
      (node (ref "IC3") (pin "4") (pinfunction "OUT_4") (pintype "passive"))
      (node (ref "JP1") (pin "2") (pinfunction "2_2") (pintype "passive"))
      (node (ref "JP3_SWD") (pin "4") (pinfunction "4_4") (pintype "passive"))
      (node (ref "R14") (pin "2") (pinfunction "2_2") (pintype "passive"))
      (node (ref "R25") (pin "1") (pinfunction "1_1") (pintype "passive"))
      (node (ref "R29") (pin "2") (pinfunction "2_2") (pintype "passive"))
      (node (ref "R30") (pin "1") (pinfunction "1_1") (pintype "passive"))
      (node (ref "R31") (pin "2") (pinfunction "2_2") (pintype "passive"))
      (node (ref "U$1") (pin "100") (pinfunction "VDD_6_100") (pintype "bidirectional"))
      (node (ref "U$1") (pin "11") (pinfunction "VDD_1_11") (pintype "bidirectional"))
      (node (ref "U$1") (pin "19") (pinfunction "VDD_2_19") (pintype "bidirectional"))
      (node (ref "U$1") (pin "22") (pinfunction "VDDA_22") (pintype "bidirectional"))
      (node (ref "U$1") (pin "28") (pinfunction "VDD_3_28") (pintype "bidirectional"))
      (node (ref "U$1") (pin "50") (pinfunction "VDD_4_50") (pintype "bidirectional"))
      (node (ref "U$1") (pin "6") (pinfunction "VBAT_6") (pintype "bidirectional"))
      (node (ref "U$1") (pin "75") (pinfunction "VDD_5_75") (pintype "bidirectional"))
      (node (ref "U1") (pin "4") (pinfunction "VCC_4") (pintype "bidirectional"))
      (node (ref "X2") (pin "1") (pinfunction "KL_1") (pintype "passive"))
    )
    (net (code "71") (name "unconnected-(U$1-PA3{slash}ETH_MII_COL{slash}ADC123_IN2(5T)-Pad26)") (class "Default")
      (node (ref "U$1") (pin "26") (pinfunction "PA3/ETH_MII_COL/ADC123_IN2(5T)_26") (pintype "bidirectional"))
    )
    (net (code "72") (name "unconnected-(U$1-PA6{slash}SPI1_MISO{slash}ADC12_IN6(5T)-Pad31)") (class "Default")
      (node (ref "U$1") (pin "31") (pinfunction "PA6/SPI1_MISO/ADC12_IN6(5T)_31") (pintype "bidirectional"))
    )
    (net (code "73") (name "unconnected-(U$1-PA7{slash}ETH_MII_RX_DV{slash}ADC12_IN7(5T)-Pad32)") (class "Default")
      (node (ref "U$1") (pin "32") (pinfunction "PA7/ETH_MII_RX_DV/ADC12_IN7(5T)_32") (pintype "bidirectional"))
    )
    (net (code "74") (name "unconnected-(U$1-PA8{slash}MCO1(5T)-Pad67)") (class "Default")
      (node (ref "U$1") (pin "67") (pinfunction "PA8/MCO1(5T)_67") (pintype "bidirectional"))
    )
    (net (code "75") (name "unconnected-(U$1-PA15{slash}JTDI(5T)-Pad77)") (class "Default")
      (node (ref "U$1") (pin "77") (pinfunction "PA15/JTDI(5T)_77") (pintype "bidirectional"))
    )
    (net (code "76") (name "unconnected-(U$1-PB0{slash}ETH_MII_RXD2{slash}ADC12_IN8(5T)-Pad35)") (class "Default")
      (node (ref "U$1") (pin "35") (pinfunction "PB0/ETH_MII_RXD2/ADC12_IN8(5T)_35") (pintype "bidirectional"))
    )
    (net (code "77") (name "unconnected-(U$1-PB1{slash}ETH_MII_RXD3{slash}ADC12_IN9(5T)-Pad36)") (class "Default")
      (node (ref "U$1") (pin "36") (pinfunction "PB1/ETH_MII_RXD3/ADC12_IN9(5T)_36") (pintype "bidirectional"))
    )
    (net (code "78") (name "unconnected-(U$1-PB3{slash}JTDO(5T)-Pad89)") (class "Default")
      (node (ref "U$1") (pin "89") (pinfunction "PB3/JTDO(5T)_89") (pintype "bidirectional"))
    )
    (net (code "79") (name "unconnected-(U$1-PB4{slash}JNTRST(5T)-Pad90)") (class "Default")
      (node (ref "U$1") (pin "90") (pinfunction "PB4/JNTRST(5T)_90") (pintype "bidirectional"))
    )
    (net (code "80") (name "unconnected-(U$1-PB8{slash}TIM10_CH1(5T)-Pad95)") (class "Default")
      (node (ref "U$1") (pin "95") (pinfunction "PB8/TIM10_CH1(5T)_95") (pintype "bidirectional"))
    )
    (net (code "81") (name "unconnected-(U$1-PB12{slash}ETH_MII_TXD0(5T)-Pad51)") (class "Default")
      (node (ref "U$1") (pin "51") (pinfunction "PB12/ETH_MII_TXD0(5T)_51") (pintype "bidirectional"))
    )
    (net (code "82") (name "unconnected-(U$1-PC0{slash}ADC123_IN10(5T)-Pad15)") (class "Default")
      (node (ref "U$1") (pin "15") (pinfunction "PC0/ADC123_IN10(5T)_15") (pintype "bidirectional"))
    )
    (net (code "83") (name "unconnected-(U$1-PC1{slash}ETH_MDC{slash}ADC123_IN11(5T)-Pad16)") (class "Default")
      (node (ref "U$1") (pin "16") (pinfunction "PC1/ETH_MDC/ADC123_IN11(5T)_16") (pintype "bidirectional"))
    )
    (net (code "84") (name "unconnected-(U$1-PC4{slash}ETH_MII_RXD0{slash}ADC12_IN14(5T)-Pad33)") (class "Default")
      (node (ref "U$1") (pin "33") (pinfunction "PC4/ETH_MII_RXD0/ADC12_IN14(5T)_33") (pintype "bidirectional"))
    )
    (net (code "85") (name "unconnected-(U$1-PC5{slash}ETH_MII_RXD1{slash}ADC12_IN15(5T)-Pad34)") (class "Default")
      (node (ref "U$1") (pin "34") (pinfunction "PC5/ETH_MII_RXD1/ADC12_IN15(5T)_34") (pintype "bidirectional"))
    )
    (net (code "86") (name "unconnected-(U$1-PC6{slash}TIM3_CH1(5T)-Pad63)") (class "Default")
      (node (ref "U$1") (pin "63") (pinfunction "PC6/TIM3_CH1(5T)_63") (pintype "bidirectional"))
    )
    (net (code "87") (name "unconnected-(U$1-PC13(5T)-Pad7)") (class "Default")
      (node (ref "U$1") (pin "7") (pinfunction "PC13(5T)_7") (pintype "bidirectional"))
    )
    (net (code "88") (name "unconnected-(U$1-PC14{slash}OSC32_IN(5T)-Pad8)") (class "Default")
      (node (ref "U$1") (pin "8") (pinfunction "PC14/OSC32_IN(5T)_8") (pintype "bidirectional"))
    )
    (net (code "89") (name "unconnected-(U$1-PC15{slash}OSC32_OUT(5T)-Pad9)") (class "Default")
      (node (ref "U$1") (pin "9") (pinfunction "PC15/OSC32_OUT(5T)_9") (pintype "bidirectional"))
    )
    (net (code "90") (name "unconnected-(U$1-PD0{slash}CAN1_RX(5T)-Pad81)") (class "Default")
      (node (ref "U$1") (pin "81") (pinfunction "PD0/CAN1_RX(5T)_81") (pintype "bidirectional"))
    )
    (net (code "91") (name "unconnected-(U$1-PD1{slash}CAN1_TX(5T)-Pad82)") (class "Default")
      (node (ref "U$1") (pin "82") (pinfunction "PD1/CAN1_TX(5T)_82") (pintype "bidirectional"))
    )
    (net (code "92") (name "unconnected-(U$1-PD3(5T)-Pad84)") (class "Default")
      (node (ref "U$1") (pin "84") (pinfunction "PD3(5T)_84") (pintype "bidirectional"))
    )
    (net (code "93") (name "unconnected-(U$1-PD4(5T)-Pad85)") (class "Default")
      (node (ref "U$1") (pin "85") (pinfunction "PD4(5T)_85") (pintype "bidirectional"))
    )
    (net (code "94") (name "unconnected-(U$1-PD5{slash}USART2_TX(5T)-Pad86)") (class "Default")
      (node (ref "U$1") (pin "86") (pinfunction "PD5/USART2_TX(5T)_86") (pintype "bidirectional"))
    )
    (net (code "95") (name "unconnected-(U$1-PD6{slash}USART2_RX(5T)-Pad87)") (class "Default")
      (node (ref "U$1") (pin "87") (pinfunction "PD6/USART2_RX(5T)_87") (pintype "bidirectional"))
    )
    (net (code "96") (name "unconnected-(U$1-PD7(5T)-Pad88)") (class "Default")
      (node (ref "U$1") (pin "88") (pinfunction "PD7(5T)_88") (pintype "bidirectional"))
    )
    (net (code "97") (name "unconnected-(U$1-PD10(5T)-Pad57)") (class "Default")
      (node (ref "U$1") (pin "57") (pinfunction "PD10(5T)_57") (pintype "bidirectional"))
    )
    (net (code "98") (name "unconnected-(U$1-PD11(5T)-Pad58)") (class "Default")
      (node (ref "U$1") (pin "58") (pinfunction "PD11(5T)_58") (pintype "bidirectional"))
    )
    (net (code "99") (name "unconnected-(U$1-PD12{slash}TIM4_CH1(5T)-Pad59)") (class "Default")
      (node (ref "U$1") (pin "59") (pinfunction "PD12/TIM4_CH1(5T)_59") (pintype "bidirectional"))
    )
    (net (code "100") (name "unconnected-(U$1-PD13{slash}TIM4_CH2(5T)-Pad60)") (class "Default")
      (node (ref "U$1") (pin "60") (pinfunction "PD13/TIM4_CH2(5T)_60") (pintype "bidirectional"))
    )
    (net (code "101") (name "unconnected-(U$1-PD14{slash}TIM4_CH3(5T)-Pad61)") (class "Default")
      (node (ref "U$1") (pin "61") (pinfunction "PD14/TIM4_CH3(5T)_61") (pintype "bidirectional"))
    )
    (net (code "102") (name "unconnected-(U$1-PD15{slash}TIM4_CH4(5T)-Pad62)") (class "Default")
      (node (ref "U$1") (pin "62") (pinfunction "PD15/TIM4_CH4(5T)_62") (pintype "bidirectional"))
    )
    (net (code "103") (name "unconnected-(U$1-VREF+-Pad21)") (class "Default")
      (node (ref "U$1") (pin "21") (pinfunction "VREF+_21") (pintype "bidirectional"))
    )
    (net (code "104") (name "unconnected-(X1C-F-Pad11)") (class "Default")
      (node (ref "X1") (pin "11") (pinfunction "F_11") (pintype "passive"))
    )
    (net (code "105") (name "unconnected-(X1D-F-Pad12)") (class "Default")
      (node (ref "X1") (pin "12") (pinfunction "F_12") (pintype "passive"))
    )
    (net (code "106") (name "unconnected-(X1G-F-Pad15)") (class "Default")
      (node (ref "X1") (pin "15") (pinfunction "F_15") (pintype "passive"))
    )
    (net (code "107") (name "unconnected-(X1J-F-Pad4)") (class "Default")
      (node (ref "X1") (pin "4") (pinfunction "F_4") (pintype "passive"))
    )
  )
)
